# Schematic.net
KiCad netlist of a schematic drawn in EasyEDA
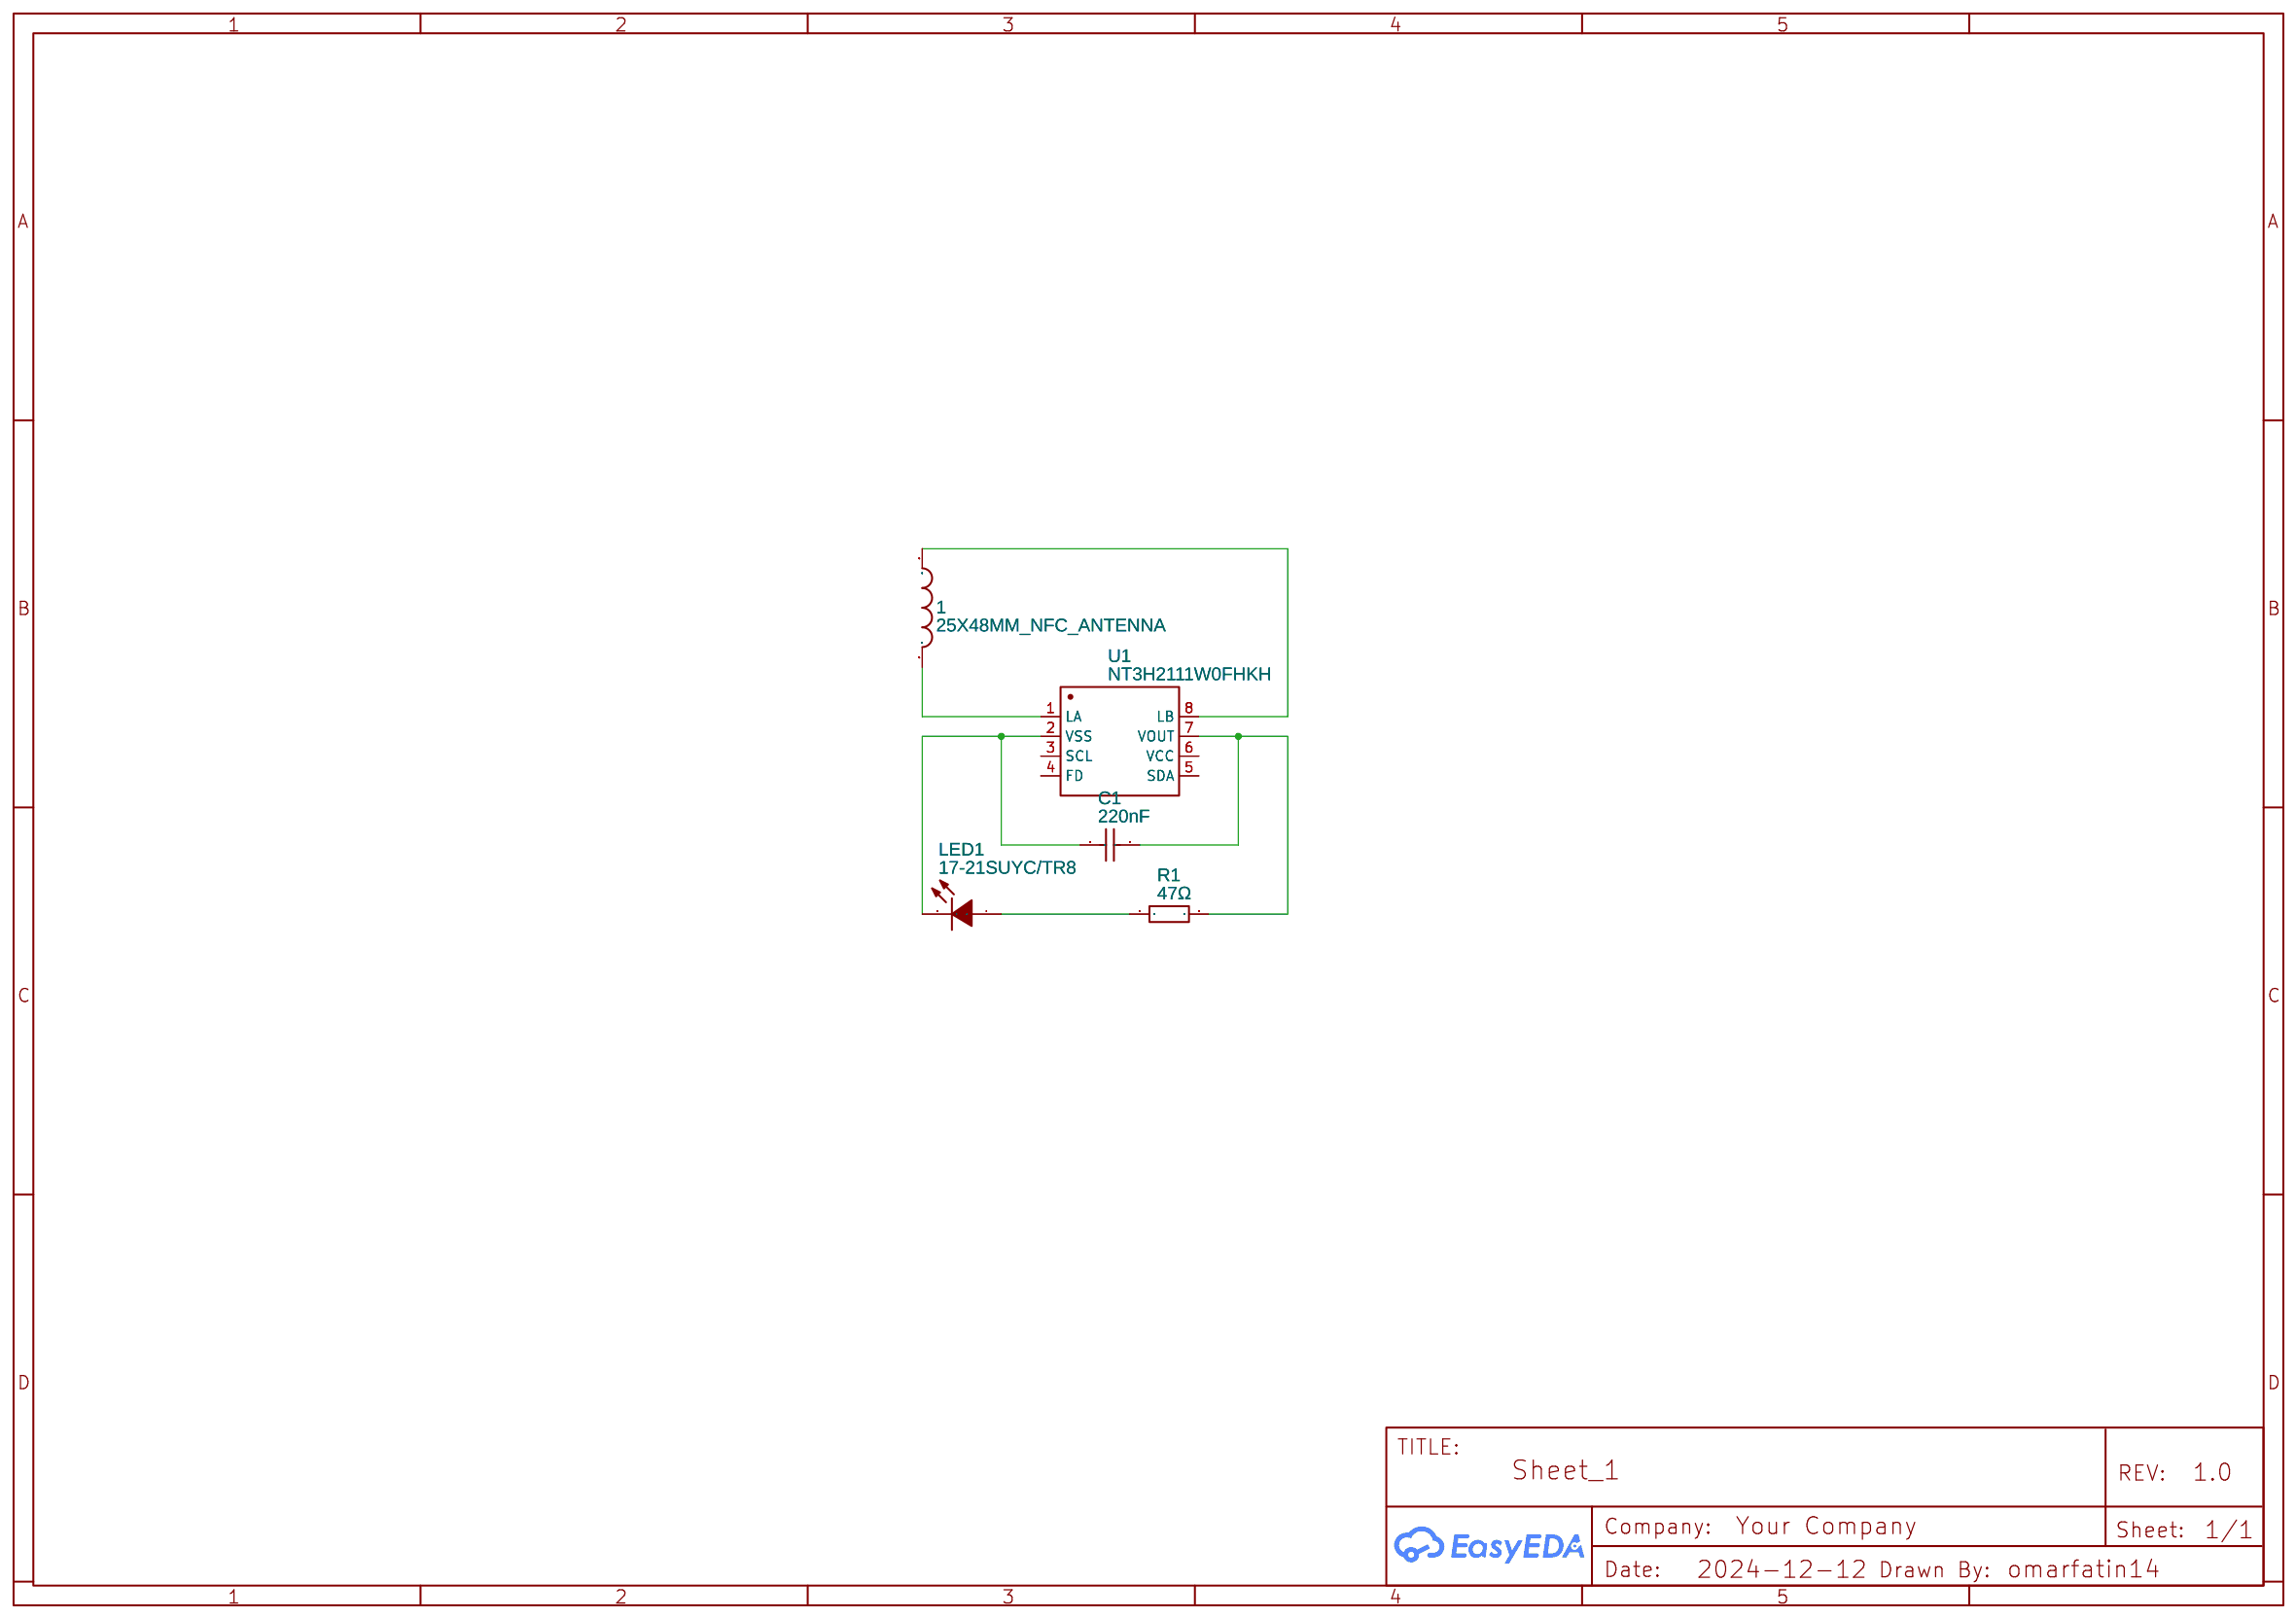
[diagram p0: schematic sheet]

(export (version "E")
  (design (tool "Eeschema 10.0.6"))
  (components
    (comp (ref "1") (value "25X48MM_NFC_ANTENNA") (libsource (lib "") (part "25X48MM_NFC_ANTENNA")))
    (comp (ref "C1")
      (value "220nF")
      (fields
        (field (name "Manufacturer Part") "CL10B224KA8NNNC")
        (field (name "Manufacturer") "SAMSUNG(三星)")
      )
      (libsource (lib "") (part "CL10B224KA8NNNC"))
    )
    (comp (ref "LED1")
      (value "17-21SUYC/TR8")
      (fields (field (name "Manufacturer Part") "KT-0805黄灯") (field (name "Manufacturer") "KENTO"))
      (libsource (lib "") (part "17-21SUYC/TR8"))
    )
    (comp (ref "R1")
      (value "47Ω")
      (fields
        (field (name "Manufacturer Part") "0603WAF470JT5E")
        (field (name "Manufacturer") "UNI-ROYAL(厚声)")
      )
      (libsource (lib "") (part "0603WAF470JT5E"))
    )
    (comp (ref "U1")
      (value "NT3H2111W0FHKH")
      (fields (field (name "Manufacturer") "NXP(恩智浦)"))
      (libsource (lib "") (part "NT3H2111W0FHKH"))
    )
  )
  (nets
    (net (code "1") (name "Net-(LED1-+)") (class "Default")
      (node (ref "LED1") (pin "1") (pinfunction "+_1") (pintype "unspecified"))
      (node (ref "R1") (pin "1") (pinfunction "1_1") (pintype "input"))
    )
    (net (code "2") (name "Net-(LED1--)") (class "Default")
      (node (ref "C1") (pin "1") (pinfunction "1_1") (pintype "input"))
      (node (ref "LED1") (pin "2") (pinfunction "-_2") (pintype "unspecified"))
      (node (ref "U1") (pin "2") (pinfunction "VSS_2") (pintype "unspecified"))
    )
    (net (code "3") (name "Net-(U1-LA)") (class "Default")
      (node (ref "1") (pin "P$2") (pinfunction "P$2_P$2") (pintype "bidirectional"))
      (node (ref "U1") (pin "1") (pinfunction "LA_1") (pintype "unspecified"))
    )
    (net (code "4") (name "Net-(U1-LB)") (class "Default")
      (node (ref "1") (pin "P$1") (pinfunction "P$1_P$1") (pintype "bidirectional"))
      (node (ref "U1") (pin "8") (pinfunction "LB_8") (pintype "unspecified"))
    )
    (net (code "5") (name "Net-(U1-VOUT)") (class "Default")
      (node (ref "C1") (pin "2") (pinfunction "2_2") (pintype "input"))
      (node (ref "R1") (pin "2") (pinfunction "2_2") (pintype "input"))
      (node (ref "U1") (pin "7") (pinfunction "VOUT_7") (pintype "unspecified"))
    )
    (net (code "6") (name "unconnected-(U1-FD-Pad4)") (class "Default")
      (node (ref "U1") (pin "4") (pinfunction "FD_4") (pintype "unspecified"))
    )
    (net (code "7") (name "unconnected-(U1-SCL-Pad3)") (class "Default")
      (node (ref "U1") (pin "3") (pinfunction "SCL_3") (pintype "unspecified"))
    )
    (net (code "8") (name "unconnected-(U1-SDA-Pad5)") (class "Default")
      (node (ref "U1") (pin "5") (pinfunction "SDA_5") (pintype "unspecified"))
    )
    (net (code "9") (name "unconnected-(U1-VCC-Pad6)") (class "Default")
      (node (ref "U1") (pin "6") (pinfunction "VCC_6") (pintype "unspecified"))
    )
  )
)
